# Boost_converter.net
KiCad netlist of a schematic drawn in Altium Designer
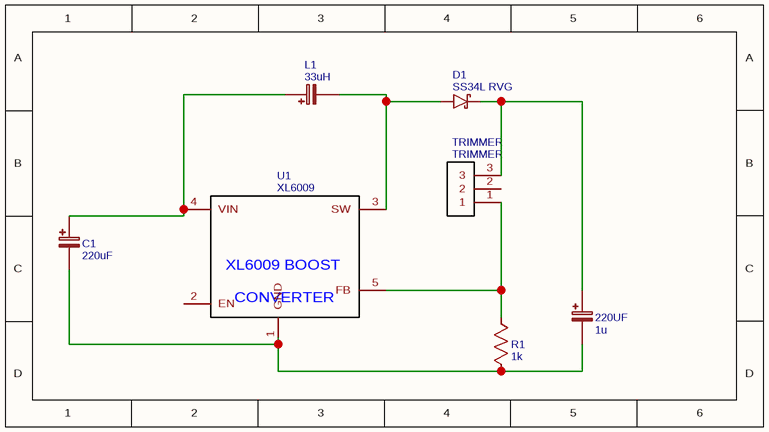
[diagram p0: Boost converter.schdoc]

(export (version "E")
  (design (tool "Eeschema 10.0.6"))
  (components
    (comp (ref "220UF")
      (value "1u")
      (fields (field (name "BOM_MANUFACTURER PART") "?") (field (name "CONTRIBUTOR") "EasyEDA"))
      (libsource (lib "altium-import") (part "root_0_1u_"))
    )
    (comp (ref "C1")
      (value "220uF")
      (fields (field (name "BOM_MANUFACTURER PART") "?") (field (name "CONTRIBUTOR") "EasyEDA"))
      (libsource (lib "altium-import") (part "root_0_220uF_"))
    )
    (comp (ref "D1")
      (value "SS34L RVG")
      (fields (field (name "BOM_MANUFACTURER PART") "?") (field (name "CONTRIBUTOR") "Junikos"))
      (libsource (lib "altium-import") (part "root_0_SS34L RVG_"))
    )
    (comp (ref "L1")
      (value "33uH")
      (fields (field (name "BOM_MANUFACTURER PART") "?") (field (name "CONTRIBUTOR") "EasyEDA"))
      (libsource (lib "altium-import") (part "root_1_33uH_"))
    )
    (comp (ref "R1")
      (value "1k")
      (fields (field (name "BOM_MANUFACTURER PART") "?"))
      (libsource (lib "altium-import") (part "root_1_1k_"))
    )
    (comp (ref "TRIMMER")
      (value "TRIMMER")
      (fields (field (name "BOM_MANUFACTURER PART") "?") (field (name "CONTRIBUTOR") "juangiraldo04"))
      (libsource (lib "altium-import") (part "root_1_TRIMMER_"))
    )
    (comp (ref "U1")
      (value "XL6009")
      (fields (field (name "CONTRIBUTOR") "GerryChen"))
      (libsource (lib "altium-import") (part "root_0_XL6009_"))
    )
  )
  (nets
    (net (code "1") (name "Net-(220UF-Pad1)") (class "Default")
      (node (ref "220UF") (pin "1") (pinfunction "1_1") (pintype "passive"))
      (node (ref "D1") (pin "2") (pinfunction "2_2") (pintype "passive"))
      (node (ref "TRIMMER") (pin "3") (pinfunction "3_3") (pintype "passive"))
    )
    (net (code "2") (name "Net-(U1-FB)") (class "Default")
      (node (ref "R1") (pin "2") (pinfunction "2_2") (pintype "passive"))
      (node (ref "TRIMMER") (pin "1") (pinfunction "1_1") (pintype "passive"))
      (node (ref "U1") (pin "5") (pinfunction "FB_5") (pintype "passive"))
    )
    (net (code "3") (name "Net-(U1-GND)") (class "Default")
      (node (ref "220UF") (pin "2") (pinfunction "2_2") (pintype "passive"))
      (node (ref "C1") (pin "2") (pinfunction "2_2") (pintype "passive"))
      (node (ref "R1") (pin "1") (pinfunction "1_1") (pintype "passive"))
      (node (ref "U1") (pin "1") (pinfunction "GND_1") (pintype "passive"))
    )
    (net (code "4") (name "Net-(U1-SW)") (class "Default")
      (node (ref "D1") (pin "1") (pinfunction "1_1") (pintype "passive"))
      (node (ref "L1") (pin "2") (pinfunction "2_2") (pintype "passive"))
      (node (ref "U1") (pin "3") (pinfunction "SW_3") (pintype "passive"))
    )
    (net (code "5") (name "Net-(U1-VIN)") (class "Default")
      (node (ref "C1") (pin "1") (pinfunction "1_1") (pintype "passive"))
      (node (ref "L1") (pin "1") (pinfunction "1_1") (pintype "passive"))
      (node (ref "U1") (pin "4") (pinfunction "VIN_4") (pintype "passive"))
    )
    (net (code "6") (name "unconnected-(TRIMMER-Pad2)") (class "Default")
      (node (ref "TRIMMER") (pin "2") (pinfunction "2_2") (pintype "passive"))
    )
    (net (code "7") (name "unconnected-(U1-EN-Pad2)") (class "Default")
      (node (ref "U1") (pin "2") (pinfunction "EN_2") (pintype "passive"))
    )
  )
)
